# final_countdown.net
KiCad netlist of a schematic drawn in EAGLE
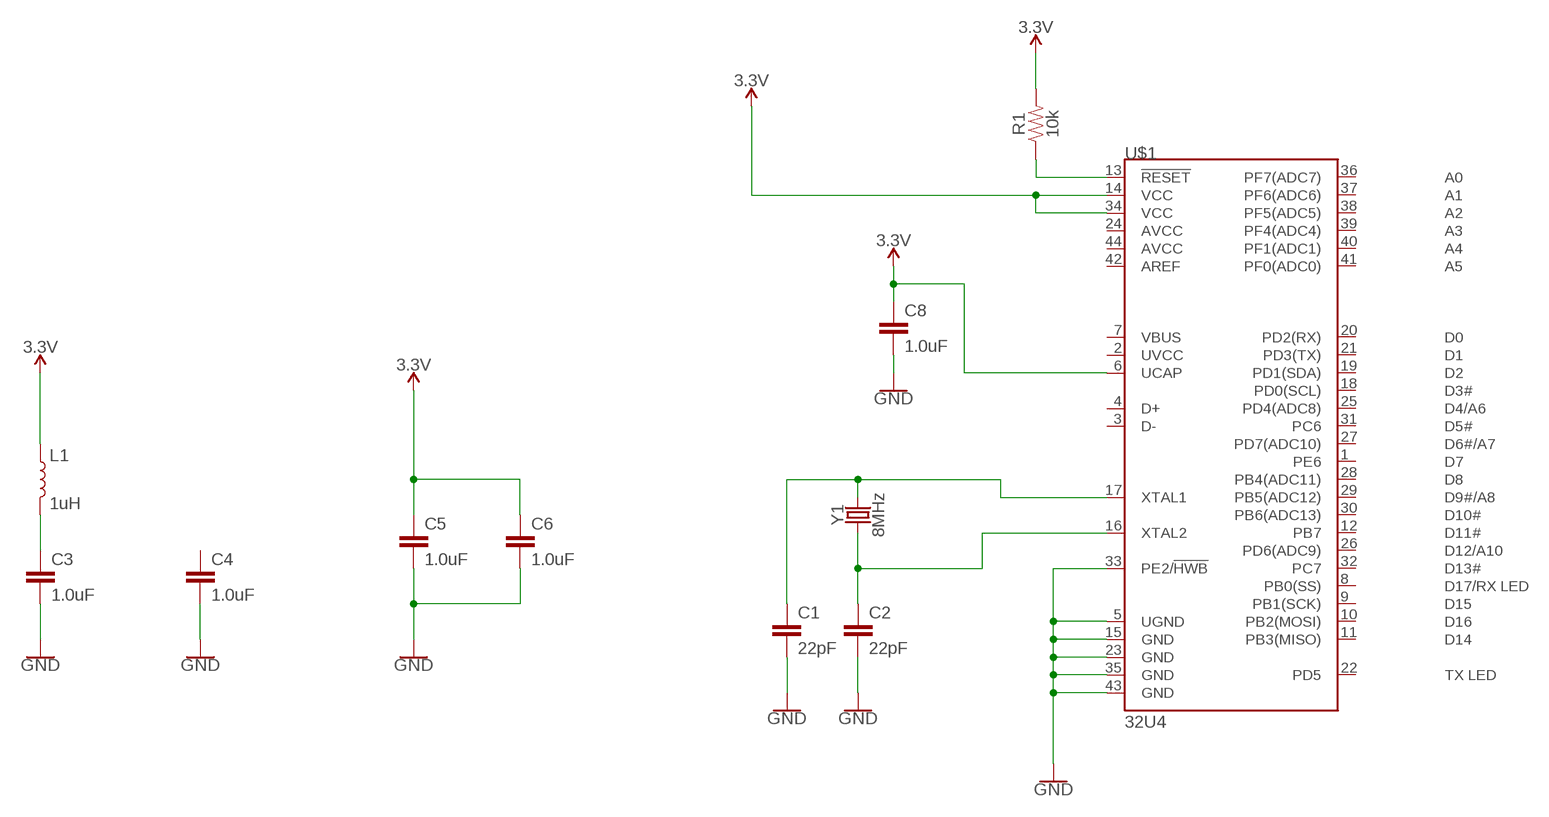
[diagram p0: schematic, sheet 1]
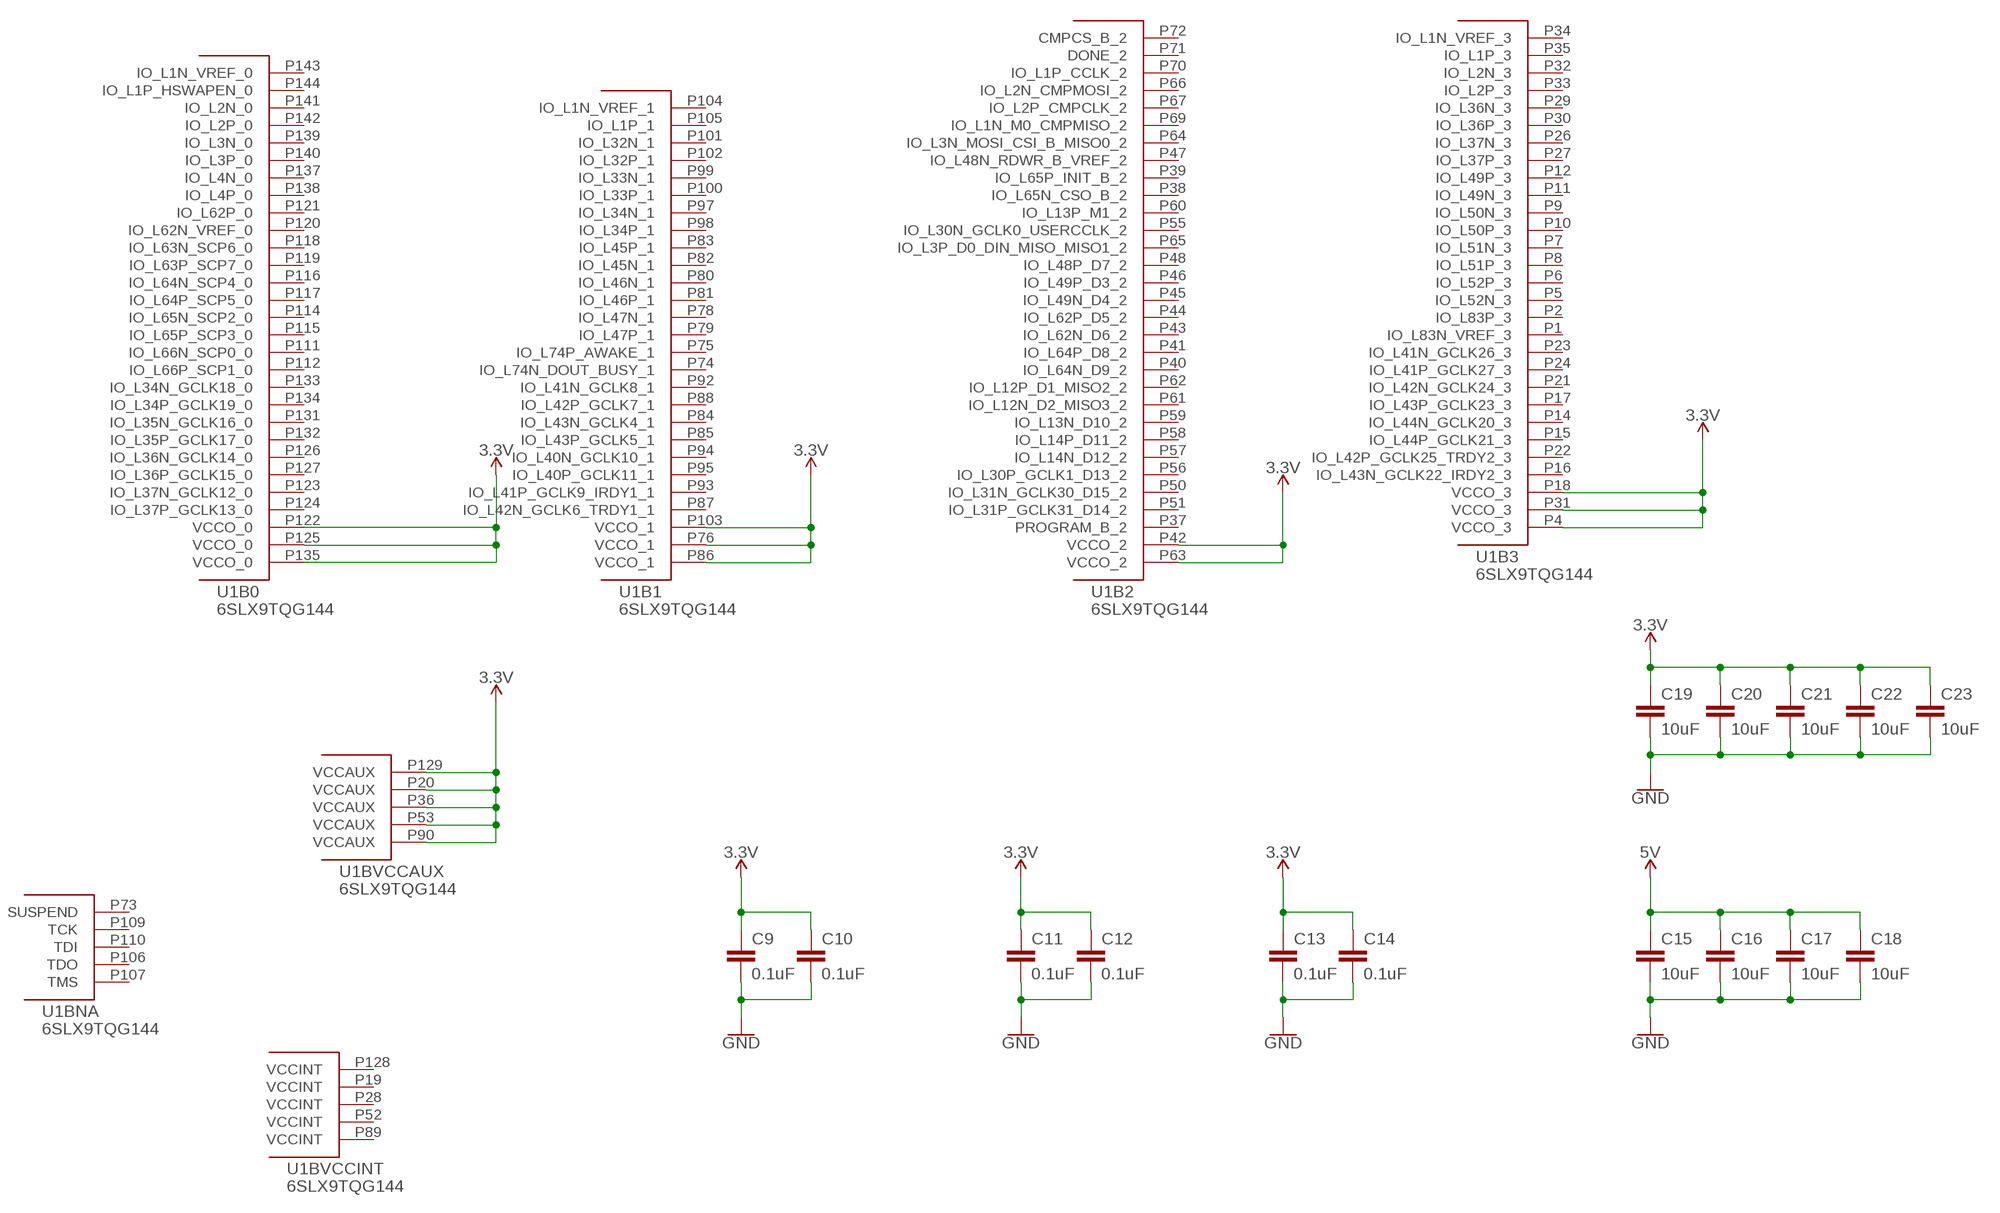
[diagram p1: schematic, sheet 2]

(export (version "E")
  (design (tool "Eeschema 10.0.6"))
  (components
    (comp (ref "C1")
      (value "22pF")
      (footprint "eagle-import:0603")
      (libsource (lib "eagle-import") (part "22PF-0603-50V-5%"))
    )
    (comp (ref "C2")
      (value "22pF")
      (footprint "eagle-import:0603")
      (libsource (lib "eagle-import") (part "22PF-0603-50V-5%"))
    )
    (comp (ref "C3")
      (value "1.0uF")
      (footprint "eagle-import:0805")
      (libsource (lib "eagle-import") (part "1.0UF-0805-25V-10%"))
    )
    (comp (ref "C4")
      (value "1.0uF")
      (footprint "eagle-import:0805")
      (libsource (lib "eagle-import") (part "1.0UF-0805-25V-10%"))
    )
    (comp (ref "C5")
      (value "1.0uF")
      (footprint "eagle-import:0805")
      (libsource (lib "eagle-import") (part "1.0UF-0805-25V-10%"))
    )
    (comp (ref "C6")
      (value "1.0uF")
      (footprint "eagle-import:0805")
      (libsource (lib "eagle-import") (part "1.0UF-0805-25V-10%"))
    )
    (comp (ref "C8")
      (value "1.0uF")
      (footprint "eagle-import:0805")
      (libsource (lib "eagle-import") (part "1.0UF-0805-25V-10%"))
    )
    (comp (ref "L1")
      (value "1uH")
      (footprint "eagle-import:INDUCTOR-SRP4020")
      (libsource (lib "eagle-import") (part "INDUCTOR-SRP4020-1UH"))
    )
    (comp (ref "R1")
      (value "10k")
      (footprint "eagle-import:0603")
      (libsource (lib "eagle-import") (part "10KOHM-0603-1/10W-1%"))
    )
    (comp (ref "U$1")
      (value "32U4")
      (footprint "eagle-import:TQFP44")
      (libsource (lib "eagle-import") (part "ATMEGA32U4TQFP-44"))
    )
    (comp (ref "Y1")
      (value "8MHz")
      (footprint "eagle-import:HC49UP")
      (libsource (lib "eagle-import") (part "CRYSTAL-8MHZSMD-HC49UP"))
    )
    (comp (ref "C9")
      (value "0.1uF")
      (footprint "eagle-import:CAP-PTH-SMALL-KIT")
      (libsource (lib "eagle-import") (part "0.1UF-KIT-EZ-50V-20%"))
    )
    (comp (ref "C10")
      (value "0.1uF")
      (footprint "eagle-import:CAP-PTH-SMALL-KIT")
      (libsource (lib "eagle-import") (part "0.1UF-KIT-EZ-50V-20%"))
    )
    (comp (ref "C11")
      (value "0.1uF")
      (footprint "eagle-import:CAP-PTH-SMALL-KIT")
      (libsource (lib "eagle-import") (part "0.1UF-KIT-EZ-50V-20%"))
    )
    (comp (ref "C12")
      (value "0.1uF")
      (footprint "eagle-import:CAP-PTH-SMALL-KIT")
      (libsource (lib "eagle-import") (part "0.1UF-KIT-EZ-50V-20%"))
    )
    (comp (ref "C13")
      (value "0.1uF")
      (footprint "eagle-import:CAP-PTH-SMALL-KIT")
      (libsource (lib "eagle-import") (part "0.1UF-KIT-EZ-50V-20%"))
    )
    (comp (ref "C14")
      (value "0.1uF")
      (footprint "eagle-import:CAP-PTH-SMALL-KIT")
      (libsource (lib "eagle-import") (part "0.1UF-KIT-EZ-50V-20%"))
    )
    (comp (ref "C15")
      (value "10uF")
      (footprint "eagle-import:0805")
      (libsource (lib "eagle-import") (part "10UF-0805-10V-10%"))
    )
    (comp (ref "C16")
      (value "10uF")
      (footprint "eagle-import:0805")
      (libsource (lib "eagle-import") (part "10UF-0805-10V-10%"))
    )
    (comp (ref "C17")
      (value "10uF")
      (footprint "eagle-import:0805")
      (libsource (lib "eagle-import") (part "10UF-0805-10V-10%"))
    )
    (comp (ref "C18")
      (value "10uF")
      (footprint "eagle-import:0805")
      (libsource (lib "eagle-import") (part "10UF-0805-10V-10%"))
    )
    (comp (ref "C19")
      (value "10uF")
      (footprint "eagle-import:0805")
      (libsource (lib "eagle-import") (part "10UF-0805-10V-10%"))
    )
    (comp (ref "C20")
      (value "10uF")
      (footprint "eagle-import:0805")
      (libsource (lib "eagle-import") (part "10UF-0805-10V-10%"))
    )
    (comp (ref "C21")
      (value "10uF")
      (footprint "eagle-import:0805")
      (libsource (lib "eagle-import") (part "10UF-0805-10V-10%"))
    )
    (comp (ref "C22")
      (value "10uF")
      (footprint "eagle-import:0805")
      (libsource (lib "eagle-import") (part "10UF-0805-10V-10%"))
    )
    (comp (ref "C23")
      (value "10uF")
      (footprint "eagle-import:0805")
      (libsource (lib "eagle-import") (part "10UF-0805-10V-10%"))
    )
    (comp (ref "U1")
      (value "6SLX9TQG144")
      (footprint "eagle-import:TQ144")
      (libsource (lib "eagle-import") (part "6SLX9TQG144"))
    )
  )
  (nets
    (net (code "1") (name "3.3V") (class "Default")
      (node (ref "C10") (pin "1") (pinfunction "1_1") (pintype "passive"))
      (node (ref "C11") (pin "1") (pinfunction "1_1") (pintype "passive"))
      (node (ref "C12") (pin "1") (pinfunction "1_1") (pintype "passive"))
      (node (ref "C13") (pin "1") (pinfunction "1_1") (pintype "passive"))
      (node (ref "C14") (pin "1") (pinfunction "1_1") (pintype "passive"))
      (node (ref "C19") (pin "1") (pinfunction "1_1") (pintype "passive"))
      (node (ref "C20") (pin "1") (pinfunction "1_1") (pintype "passive"))
      (node (ref "C21") (pin "1") (pinfunction "1_1") (pintype "passive"))
      (node (ref "C22") (pin "1") (pinfunction "1_1") (pintype "passive"))
      (node (ref "C23") (pin "1") (pinfunction "1_1") (pintype "passive"))
      (node (ref "C5") (pin "1") (pinfunction "1_1") (pintype "passive"))
      (node (ref "C6") (pin "1") (pinfunction "1_1") (pintype "passive"))
      (node (ref "C8") (pin "1") (pinfunction "1_1") (pintype "passive"))
      (node (ref "C9") (pin "1") (pinfunction "1_1") (pintype "passive"))
      (node (ref "L1") (pin "P$1") (pinfunction "1_P$1") (pintype "passive"))
      (node (ref "R1") (pin "2") (pinfunction "2_2") (pintype "passive"))
      (node (ref "U$1") (pin "14") (pinfunction "VCC_14") (pintype "bidirectional"))
      (node (ref "U$1") (pin "34") (pinfunction "VCC_34") (pintype "bidirectional"))
      (node (ref "U$1") (pin "6") (pinfunction "UCAP_6") (pintype "bidirectional"))
      (node (ref "U1") (pin "P103") (pinfunction "VCCO_1_P103") (pintype "input"))
      (node (ref "U1") (pin "P122") (pinfunction "VCCO_0_P122") (pintype "input"))
      (node (ref "U1") (pin "P125") (pinfunction "VCCO_0_P125") (pintype "input"))
      (node (ref "U1") (pin "P129") (pinfunction "VCCAUX_P129") (pintype "input"))
      (node (ref "U1") (pin "P135") (pinfunction "VCCO_0_P135") (pintype "input"))
      (node (ref "U1") (pin "P18") (pinfunction "VCCO_3_P18") (pintype "input"))
      (node (ref "U1") (pin "P20") (pinfunction "VCCAUX_P20") (pintype "input"))
      (node (ref "U1") (pin "P31") (pinfunction "VCCO_3_P31") (pintype "input"))
      (node (ref "U1") (pin "P36") (pinfunction "VCCAUX_P36") (pintype "input"))
      (node (ref "U1") (pin "P4") (pinfunction "VCCO_3_P4") (pintype "input"))
      (node (ref "U1") (pin "P42") (pinfunction "VCCO_2_P42") (pintype "input"))
      (node (ref "U1") (pin "P53") (pinfunction "VCCAUX_P53") (pintype "input"))
      (node (ref "U1") (pin "P63") (pinfunction "VCCO_2_P63") (pintype "input"))
      (node (ref "U1") (pin "P76") (pinfunction "VCCO_1_P76") (pintype "input"))
      (node (ref "U1") (pin "P86") (pinfunction "VCCO_1_P86") (pintype "input"))
      (node (ref "U1") (pin "P90") (pinfunction "VCCAUX_P90") (pintype "input"))
    )
    (net (code "2") (name "5V") (class "Default")
      (node (ref "C15") (pin "1") (pinfunction "1_1") (pintype "passive"))
      (node (ref "C16") (pin "1") (pinfunction "1_1") (pintype "passive"))
      (node (ref "C17") (pin "1") (pinfunction "1_1") (pintype "passive"))
      (node (ref "C18") (pin "1") (pinfunction "1_1") (pintype "passive"))
    )
    (net (code "3") (name "GND") (class "Default")
      (node (ref "C1") (pin "2") (pinfunction "2_2") (pintype "passive"))
      (node (ref "C10") (pin "2") (pinfunction "2_2") (pintype "passive"))
      (node (ref "C11") (pin "2") (pinfunction "2_2") (pintype "passive"))
      (node (ref "C12") (pin "2") (pinfunction "2_2") (pintype "passive"))
      (node (ref "C13") (pin "2") (pinfunction "2_2") (pintype "passive"))
      (node (ref "C14") (pin "2") (pinfunction "2_2") (pintype "passive"))
      (node (ref "C15") (pin "2") (pinfunction "2_2") (pintype "passive"))
      (node (ref "C16") (pin "2") (pinfunction "2_2") (pintype "passive"))
      (node (ref "C17") (pin "2") (pinfunction "2_2") (pintype "passive"))
      (node (ref "C18") (pin "2") (pinfunction "2_2") (pintype "passive"))
      (node (ref "C19") (pin "2") (pinfunction "2_2") (pintype "passive"))
      (node (ref "C2") (pin "2") (pinfunction "2_2") (pintype "passive"))
      (node (ref "C20") (pin "2") (pinfunction "2_2") (pintype "passive"))
      (node (ref "C21") (pin "2") (pinfunction "2_2") (pintype "passive"))
      (node (ref "C22") (pin "2") (pinfunction "2_2") (pintype "passive"))
      (node (ref "C23") (pin "2") (pinfunction "2_2") (pintype "passive"))
      (node (ref "C3") (pin "2") (pinfunction "2_2") (pintype "passive"))
      (node (ref "C4") (pin "2") (pinfunction "2_2") (pintype "passive"))
      (node (ref "C5") (pin "2") (pinfunction "2_2") (pintype "passive"))
      (node (ref "C6") (pin "2") (pinfunction "2_2") (pintype "passive"))
      (node (ref "C8") (pin "2") (pinfunction "2_2") (pintype "passive"))
      (node (ref "C9") (pin "2") (pinfunction "2_2") (pintype "passive"))
      (node (ref "U$1") (pin "15") (pinfunction "GND_15") (pintype "bidirectional"))
      (node (ref "U$1") (pin "23") (pinfunction "GND_23") (pintype "bidirectional"))
      (node (ref "U$1") (pin "33") (pinfunction "PE2/~{HWB}_33") (pintype "bidirectional"))
      (node (ref "U$1") (pin "35") (pinfunction "GND_35") (pintype "bidirectional"))
      (node (ref "U$1") (pin "43") (pinfunction "GND_43") (pintype "bidirectional"))
      (node (ref "U$1") (pin "5") (pinfunction "UGND_5") (pintype "bidirectional"))
    )
    (net (code "4") (name "Net-(L1-2)") (class "Default")
      (node (ref "C3") (pin "1") (pinfunction "1_1") (pintype "passive"))
      (node (ref "L1") (pin "P$2") (pinfunction "2_P$2") (pintype "passive"))
    )
    (net (code "5") (name "Net-(U$1-XTAL1)") (class "Default")
      (node (ref "C1") (pin "1") (pinfunction "1_1") (pintype "passive"))
      (node (ref "U$1") (pin "17") (pinfunction "XTAL1_17") (pintype "bidirectional"))
      (node (ref "Y1") (pin "2") (pinfunction "2_2") (pintype "passive"))
    )
    (net (code "6") (name "Net-(U$1-XTAL2)") (class "Default")
      (node (ref "C2") (pin "1") (pinfunction "1_1") (pintype "passive"))
      (node (ref "U$1") (pin "16") (pinfunction "XTAL2_16") (pintype "bidirectional"))
      (node (ref "Y1") (pin "1") (pinfunction "1_1") (pintype "passive"))
    )
    (net (code "7") (name "Net-(U$1-~{RESET})") (class "Default")
      (node (ref "R1") (pin "1") (pinfunction "1_1") (pintype "passive"))
      (node (ref "U$1") (pin "13") (pinfunction "~{RESET}_13") (pintype "bidirectional"))
    )
    (net (code "8") (name "unconnected-(C4-Pad1)") (class "Default")
      (node (ref "C4") (pin "1") (pinfunction "1_1") (pintype "passive"))
    )
    (net (code "9") (name "unconnected-(U$1-AREF-Pad42)") (class "Default")
      (node (ref "U$1") (pin "42") (pinfunction "AREF_42") (pintype "bidirectional"))
    )
    (net (code "10") (name "unconnected-(U$1-AVCC-Pad24)") (class "Default")
      (node (ref "U$1") (pin "24") (pinfunction "AVCC_24") (pintype "bidirectional"))
    )
    (net (code "11") (name "unconnected-(U$1-AVCC-Pad44)") (class "Default")
      (node (ref "U$1") (pin "44") (pinfunction "AVCC_44") (pintype "bidirectional"))
    )
    (net (code "12") (name "unconnected-(U$1-D+-Pad4)") (class "Default")
      (node (ref "U$1") (pin "4") (pinfunction "D+_4") (pintype "bidirectional"))
    )
    (net (code "13") (name "unconnected-(U$1-D--Pad3)") (class "Default")
      (node (ref "U$1") (pin "3") (pinfunction "D-_3") (pintype "bidirectional"))
    )
    (net (code "14") (name "unconnected-(U$1-PB0(SS)-Pad8)") (class "Default")
      (node (ref "U$1") (pin "8") (pinfunction "PB0(SS)_8") (pintype "bidirectional"))
    )
    (net (code "15") (name "unconnected-(U$1-PB1(SCK)-Pad9)") (class "Default")
      (node (ref "U$1") (pin "9") (pinfunction "PB1(SCK)_9") (pintype "bidirectional"))
    )
    (net (code "16") (name "unconnected-(U$1-PB2(MOSI)-Pad10)") (class "Default")
      (node (ref "U$1") (pin "10") (pinfunction "PB2(MOSI)_10") (pintype "bidirectional"))
    )
    (net (code "17") (name "unconnected-(U$1-PB3(MISO)-Pad11)") (class "Default")
      (node (ref "U$1") (pin "11") (pinfunction "PB3(MISO)_11") (pintype "bidirectional"))
    )
    (net (code "18") (name "unconnected-(U$1-PB4(ADC11)-Pad28)") (class "Default")
      (node (ref "U$1") (pin "28") (pinfunction "PB4(ADC11)_28") (pintype "bidirectional"))
    )
    (net (code "19") (name "unconnected-(U$1-PB5(ADC12)-Pad29)") (class "Default")
      (node (ref "U$1") (pin "29") (pinfunction "PB5(ADC12)_29") (pintype "bidirectional"))
    )
    (net (code "20") (name "unconnected-(U$1-PB6(ADC13)-Pad30)") (class "Default")
      (node (ref "U$1") (pin "30") (pinfunction "PB6(ADC13)_30") (pintype "bidirectional"))
    )
    (net (code "21") (name "unconnected-(U$1-PB7-Pad12)") (class "Default")
      (node (ref "U$1") (pin "12") (pinfunction "PB7_12") (pintype "bidirectional"))
    )
    (net (code "22") (name "unconnected-(U$1-PC6-Pad31)") (class "Default")
      (node (ref "U$1") (pin "31") (pinfunction "PC6_31") (pintype "bidirectional"))
    )
    (net (code "23") (name "unconnected-(U$1-PC7-Pad32)") (class "Default")
      (node (ref "U$1") (pin "32") (pinfunction "PC7_32") (pintype "bidirectional"))
    )
    (net (code "24") (name "unconnected-(U$1-PD0(SCL)-Pad18)") (class "Default")
      (node (ref "U$1") (pin "18") (pinfunction "PD0(SCL)_18") (pintype "bidirectional"))
    )
    (net (code "25") (name "unconnected-(U$1-PD1(SDA)-Pad19)") (class "Default")
      (node (ref "U$1") (pin "19") (pinfunction "PD1(SDA)_19") (pintype "bidirectional"))
    )
    (net (code "26") (name "unconnected-(U$1-PD2(RX)-Pad20)") (class "Default")
      (node (ref "U$1") (pin "20") (pinfunction "PD2(RX)_20") (pintype "bidirectional"))
    )
    (net (code "27") (name "unconnected-(U$1-PD3(TX)-Pad21)") (class "Default")
      (node (ref "U$1") (pin "21") (pinfunction "PD3(TX)_21") (pintype "bidirectional"))
    )
    (net (code "28") (name "unconnected-(U$1-PD4(ADC8)-Pad25)") (class "Default")
      (node (ref "U$1") (pin "25") (pinfunction "PD4(ADC8)_25") (pintype "bidirectional"))
    )
    (net (code "29") (name "unconnected-(U$1-PD5-Pad22)") (class "Default")
      (node (ref "U$1") (pin "22") (pinfunction "PD5_22") (pintype "bidirectional"))
    )
    (net (code "30") (name "unconnected-(U$1-PD6(ADC9)-Pad26)") (class "Default")
      (node (ref "U$1") (pin "26") (pinfunction "PD6(ADC9)_26") (pintype "bidirectional"))
    )
    (net (code "31") (name "unconnected-(U$1-PD7(ADC10)-Pad27)") (class "Default")
      (node (ref "U$1") (pin "27") (pinfunction "PD7(ADC10)_27") (pintype "bidirectional"))
    )
    (net (code "32") (name "unconnected-(U$1-PE6-Pad1)") (class "Default")
      (node (ref "U$1") (pin "1") (pinfunction "PE6_1") (pintype "bidirectional"))
    )
    (net (code "33") (name "unconnected-(U$1-PF0(ADC0)-Pad41)") (class "Default")
      (node (ref "U$1") (pin "41") (pinfunction "PF0(ADC0)_41") (pintype "bidirectional"))
    )
    (net (code "34") (name "unconnected-(U$1-PF1(ADC1)-Pad40)") (class "Default")
      (node (ref "U$1") (pin "40") (pinfunction "PF1(ADC1)_40") (pintype "bidirectional"))
    )
    (net (code "35") (name "unconnected-(U$1-PF4(ADC4)-Pad39)") (class "Default")
      (node (ref "U$1") (pin "39") (pinfunction "PF4(ADC4)_39") (pintype "bidirectional"))
    )
    (net (code "36") (name "unconnected-(U$1-PF5(ADC5)-Pad38)") (class "Default")
      (node (ref "U$1") (pin "38") (pinfunction "PF5(ADC5)_38") (pintype "bidirectional"))
    )
    (net (code "37") (name "unconnected-(U$1-PF6(ADC6)-Pad37)") (class "Default")
      (node (ref "U$1") (pin "37") (pinfunction "PF6(ADC6)_37") (pintype "bidirectional"))
    )
    (net (code "38") (name "unconnected-(U$1-PF7(ADC7)-Pad36)") (class "Default")
      (node (ref "U$1") (pin "36") (pinfunction "PF7(ADC7)_36") (pintype "bidirectional"))
    )
    (net (code "39") (name "unconnected-(U$1-UVCC-Pad2)") (class "Default")
      (node (ref "U$1") (pin "2") (pinfunction "UVCC_2") (pintype "bidirectional"))
    )
    (net (code "40") (name "unconnected-(U$1-VBUS-Pad7)") (class "Default")
      (node (ref "U$1") (pin "7") (pinfunction "VBUS_7") (pintype "bidirectional"))
    )
    (net (code "41") (name "unconnected-(U1A-IO_L1N_VREF_0-PadP143)") (class "Default")
      (node (ref "U1") (pin "P143") (pinfunction "IO_L1N_VREF_0_P143") (pintype "bidirectional"))
    )
    (net (code "42") (name "unconnected-(U1A-IO_L1P_HSWAPEN_0-PadP144)") (class "Default")
      (node (ref "U1") (pin "P144") (pinfunction "IO_L1P_HSWAPEN_0_P144") (pintype "bidirectional"))
    )
    (net (code "43") (name "unconnected-(U1A-IO_L2N_0-PadP141)") (class "Default")
      (node (ref "U1") (pin "P141") (pinfunction "IO_L2N_0_P141") (pintype "bidirectional"))
    )
    (net (code "44") (name "unconnected-(U1A-IO_L2P_0-PadP142)") (class "Default")
      (node (ref "U1") (pin "P142") (pinfunction "IO_L2P_0_P142") (pintype "bidirectional"))
    )
    (net (code "45") (name "unconnected-(U1A-IO_L3N_0-PadP139)") (class "Default")
      (node (ref "U1") (pin "P139") (pinfunction "IO_L3N_0_P139") (pintype "bidirectional"))
    )
    (net (code "46") (name "unconnected-(U1A-IO_L3P_0-PadP140)") (class "Default")
      (node (ref "U1") (pin "P140") (pinfunction "IO_L3P_0_P140") (pintype "bidirectional"))
    )
    (net (code "47") (name "unconnected-(U1A-IO_L4N_0-PadP137)") (class "Default")
      (node (ref "U1") (pin "P137") (pinfunction "IO_L4N_0_P137") (pintype "bidirectional"))
    )
    (net (code "48") (name "unconnected-(U1A-IO_L4P_0-PadP138)") (class "Default")
      (node (ref "U1") (pin "P138") (pinfunction "IO_L4P_0_P138") (pintype "bidirectional"))
    )
    (net (code "49") (name "unconnected-(U1A-IO_L34N_GCLK18_0-PadP133)") (class "Default")
      (node (ref "U1") (pin "P133") (pinfunction "IO_L34N_GCLK18_0_P133") (pintype "bidirectional"))
    )
    (net (code "50") (name "unconnected-(U1A-IO_L34P_GCLK19_0-PadP134)") (class "Default")
      (node (ref "U1") (pin "P134") (pinfunction "IO_L34P_GCLK19_0_P134") (pintype "bidirectional"))
    )
    (net (code "51") (name "unconnected-(U1A-IO_L35N_GCLK16_0-PadP131)") (class "Default")
      (node (ref "U1") (pin "P131") (pinfunction "IO_L35N_GCLK16_0_P131") (pintype "bidirectional"))
    )
    (net (code "52") (name "unconnected-(U1A-IO_L35P_GCLK17_0-PadP132)") (class "Default")
      (node (ref "U1") (pin "P132") (pinfunction "IO_L35P_GCLK17_0_P132") (pintype "bidirectional"))
    )
    (net (code "53") (name "unconnected-(U1A-IO_L36N_GCLK14_0-PadP126)") (class "Default")
      (node (ref "U1") (pin "P126") (pinfunction "IO_L36N_GCLK14_0_P126") (pintype "bidirectional"))
    )
    (net (code "54") (name "unconnected-(U1A-IO_L36P_GCLK15_0-PadP127)") (class "Default")
      (node (ref "U1") (pin "P127") (pinfunction "IO_L36P_GCLK15_0_P127") (pintype "bidirectional"))
    )
    (net (code "55") (name "unconnected-(U1A-IO_L37N_GCLK12_0-PadP123)") (class "Default")
      (node (ref "U1") (pin "P123") (pinfunction "IO_L37N_GCLK12_0_P123") (pintype "bidirectional"))
    )
    (net (code "56") (name "unconnected-(U1A-IO_L37P_GCLK13_0-PadP124)") (class "Default")
      (node (ref "U1") (pin "P124") (pinfunction "IO_L37P_GCLK13_0_P124") (pintype "bidirectional"))
    )
    (net (code "57") (name "unconnected-(U1A-IO_L62N_VREF_0-PadP120)") (class "Default")
      (node (ref "U1") (pin "P120") (pinfunction "IO_L62N_VREF_0_P120") (pintype "bidirectional"))
    )
    (net (code "58") (name "unconnected-(U1A-IO_L62P_0-PadP121)") (class "Default")
      (node (ref "U1") (pin "P121") (pinfunction "IO_L62P_0_P121") (pintype "bidirectional"))
    )
    (net (code "59") (name "unconnected-(U1A-IO_L63N_SCP6_0-PadP118)") (class "Default")
      (node (ref "U1") (pin "P118") (pinfunction "IO_L63N_SCP6_0_P118") (pintype "bidirectional"))
    )
    (net (code "60") (name "unconnected-(U1A-IO_L63P_SCP7_0-PadP119)") (class "Default")
      (node (ref "U1") (pin "P119") (pinfunction "IO_L63P_SCP7_0_P119") (pintype "bidirectional"))
    )
    (net (code "61") (name "unconnected-(U1A-IO_L64N_SCP4_0-PadP116)") (class "Default")
      (node (ref "U1") (pin "P116") (pinfunction "IO_L64N_SCP4_0_P116") (pintype "bidirectional"))
    )
    (net (code "62") (name "unconnected-(U1A-IO_L64P_SCP5_0-PadP117)") (class "Default")
      (node (ref "U1") (pin "P117") (pinfunction "IO_L64P_SCP5_0_P117") (pintype "bidirectional"))
    )
    (net (code "63") (name "unconnected-(U1A-IO_L65N_SCP2_0-PadP114)") (class "Default")
      (node (ref "U1") (pin "P114") (pinfunction "IO_L65N_SCP2_0_P114") (pintype "bidirectional"))
    )
    (net (code "64") (name "unconnected-(U1A-IO_L65P_SCP3_0-PadP115)") (class "Default")
      (node (ref "U1") (pin "P115") (pinfunction "IO_L65P_SCP3_0_P115") (pintype "bidirectional"))
    )
    (net (code "65") (name "unconnected-(U1A-IO_L66N_SCP0_0-PadP111)") (class "Default")
      (node (ref "U1") (pin "P111") (pinfunction "IO_L66N_SCP0_0_P111") (pintype "bidirectional"))
    )
    (net (code "66") (name "unconnected-(U1A-IO_L66P_SCP1_0-PadP112)") (class "Default")
      (node (ref "U1") (pin "P112") (pinfunction "IO_L66P_SCP1_0_P112") (pintype "bidirectional"))
    )
    (net (code "67") (name "unconnected-(U1B-IO_L1N_VREF_1-PadP104)") (class "Default")
      (node (ref "U1") (pin "P104") (pinfunction "IO_L1N_VREF_1_P104") (pintype "bidirectional"))
    )
    (net (code "68") (name "unconnected-(U1B-IO_L1P_1-PadP105)") (class "Default")
      (node (ref "U1") (pin "P105") (pinfunction "IO_L1P_1_P105") (pintype "bidirectional"))
    )
    (net (code "69") (name "unconnected-(U1B-IO_L32N_1-PadP101)") (class "Default")
      (node (ref "U1") (pin "P101") (pinfunction "IO_L32N_1_P101") (pintype "bidirectional"))
    )
    (net (code "70") (name "unconnected-(U1B-IO_L32P_1-PadP102)") (class "Default")
      (node (ref "U1") (pin "P102") (pinfunction "IO_L32P_1_P102") (pintype "bidirectional"))
    )
    (net (code "71") (name "unconnected-(U1B-IO_L33N_1-PadP99)") (class "Default")
      (node (ref "U1") (pin "P99") (pinfunction "IO_L33N_1_P99") (pintype "bidirectional"))
    )
    (net (code "72") (name "unconnected-(U1B-IO_L33P_1-PadP100)") (class "Default")
      (node (ref "U1") (pin "P100") (pinfunction "IO_L33P_1_P100") (pintype "bidirectional"))
    )
    (net (code "73") (name "unconnected-(U1B-IO_L34N_1-PadP97)") (class "Default")
      (node (ref "U1") (pin "P97") (pinfunction "IO_L34N_1_P97") (pintype "bidirectional"))
    )
    (net (code "74") (name "unconnected-(U1B-IO_L34P_1-PadP98)") (class "Default")
      (node (ref "U1") (pin "P98") (pinfunction "IO_L34P_1_P98") (pintype "bidirectional"))
    )
    (net (code "75") (name "unconnected-(U1B-IO_L40N_GCLK10_1-PadP94)") (class "Default")
      (node (ref "U1") (pin "P94") (pinfunction "IO_L40N_GCLK10_1_P94") (pintype "bidirectional"))
    )
    (net (code "76") (name "unconnected-(U1B-IO_L40P_GCLK11_1-PadP95)") (class "Default")
      (node (ref "U1") (pin "P95") (pinfunction "IO_L40P_GCLK11_1_P95") (pintype "bidirectional"))
    )
    (net (code "77") (name "unconnected-(U1B-IO_L41N_GCLK8_1-PadP92)") (class "Default")
      (node (ref "U1") (pin "P92") (pinfunction "IO_L41N_GCLK8_1_P92") (pintype "bidirectional"))
    )
    (net (code "78") (name "unconnected-(U1B-IO_L41P_GCLK9_IRDY1_1-PadP93)") (class "Default")
      (node (ref "U1") (pin "P93") (pinfunction "IO_L41P_GCLK9_IRDY1_1_P93") (pintype "bidirectional"))
    )
    (net (code "79") (name "unconnected-(U1B-IO_L42N_GCLK6_TRDY1_1-PadP87)") (class "Default")
      (node (ref "U1") (pin "P87") (pinfunction "IO_L42N_GCLK6_TRDY1_1_P87") (pintype "bidirectional"))
    )
    (net (code "80") (name "unconnected-(U1B-IO_L42P_GCLK7_1-PadP88)") (class "Default")
      (node (ref "U1") (pin "P88") (pinfunction "IO_L42P_GCLK7_1_P88") (pintype "bidirectional"))
    )
    (net (code "81") (name "unconnected-(U1B-IO_L43N_GCLK4_1-PadP84)") (class "Default")
      (node (ref "U1") (pin "P84") (pinfunction "IO_L43N_GCLK4_1_P84") (pintype "bidirectional"))
    )
    (net (code "82") (name "unconnected-(U1B-IO_L43P_GCLK5_1-PadP85)") (class "Default")
      (node (ref "U1") (pin "P85") (pinfunction "IO_L43P_GCLK5_1_P85") (pintype "bidirectional"))
    )
    (net (code "83") (name "unconnected-(U1B-IO_L45N_1-PadP82)") (class "Default")
      (node (ref "U1") (pin "P82") (pinfunction "IO_L45N_1_P82") (pintype "bidirectional"))
    )
    (net (code "84") (name "unconnected-(U1B-IO_L45P_1-PadP83)") (class "Default")
      (node (ref "U1") (pin "P83") (pinfunction "IO_L45P_1_P83") (pintype "bidirectional"))
    )
    (net (code "85") (name "unconnected-(U1B-IO_L46N_1-PadP80)") (class "Default")
      (node (ref "U1") (pin "P80") (pinfunction "IO_L46N_1_P80") (pintype "bidirectional"))
    )
    (net (code "86") (name "unconnected-(U1B-IO_L46P_1-PadP81)") (class "Default")
      (node (ref "U1") (pin "P81") (pinfunction "IO_L46P_1_P81") (pintype "bidirectional"))
    )
    (net (code "87") (name "unconnected-(U1B-IO_L47N_1-PadP78)") (class "Default")
      (node (ref "U1") (pin "P78") (pinfunction "IO_L47N_1_P78") (pintype "bidirectional"))
    )
    (net (code "88") (name "unconnected-(U1B-IO_L47P_1-PadP79)") (class "Default")
      (node (ref "U1") (pin "P79") (pinfunction "IO_L47P_1_P79") (pintype "bidirectional"))
    )
    (net (code "89") (name "unconnected-(U1B-IO_L74N_DOUT_BUSY_1-PadP74)") (class "Default")
      (node (ref "U1") (pin "P74") (pinfunction "IO_L74N_DOUT_BUSY_1_P74") (pintype "bidirectional"))
    )
    (net (code "90") (name "unconnected-(U1B-IO_L74P_AWAKE_1-PadP75)") (class "Default")
      (node (ref "U1") (pin "P75") (pinfunction "IO_L74P_AWAKE_1_P75") (pintype "bidirectional"))
    )
    (net (code "91") (name "unconnected-(U1C-CMPCS_B_2-PadP72)") (class "Default")
      (node (ref "U1") (pin "P72") (pinfunction "CMPCS_B_2_P72") (pintype "bidirectional"))
    )
    (net (code "92") (name "unconnected-(U1C-DONE_2-PadP71)") (class "Default")
      (node (ref "U1") (pin "P71") (pinfunction "DONE_2_P71") (pintype "bidirectional"))
    )
    (net (code "93") (name "unconnected-(U1C-IO_L1N_M0_CMPMISO_2-PadP69)") (class "Default")
      (node (ref "U1") (pin "P69") (pinfunction "IO_L1N_M0_CMPMISO_2_P69") (pintype "bidirectional"))
    )
    (net (code "94") (name "unconnected-(U1C-IO_L1P_CCLK_2-PadP70)") (class "Default")
      (node (ref "U1") (pin "P70") (pinfunction "IO_L1P_CCLK_2_P70") (pintype "bidirectional"))
    )
    (net (code "95") (name "unconnected-(U1C-IO_L2N_CMPMOSI_2-PadP66)") (class "Default")
      (node (ref "U1") (pin "P66") (pinfunction "IO_L2N_CMPMOSI_2_P66") (pintype "bidirectional"))
    )
    (net (code "96") (name "unconnected-(U1C-IO_L2P_CMPCLK_2-PadP67)") (class "Default")
      (node (ref "U1") (pin "P67") (pinfunction "IO_L2P_CMPCLK_2_P67") (pintype "bidirectional"))
    )
    (net (code "97") (name "unconnected-(U1C-IO_L3N_MOSI_CSI_B_MISO0_2-PadP64)") (class "Default")
      (node (ref "U1") (pin "P64") (pinfunction "IO_L3N_MOSI_CSI_B_MISO0_2_P64") (pintype "bidirectional"))
    )
    (net (code "98") (name "unconnected-(U1C-IO_L3P_D0_DIN_MISO_MISO1_2-PadP65)") (class "Default")
      (node (ref "U1") (pin "P65") (pinfunction "IO_L3P_D0_DIN_MISO_MISO1_2_P65") (pintype "bidirectional"))
    )
    (net (code "99") (name "unconnected-(U1C-IO_L12N_D2_MISO3_2-PadP61)") (class "Default")
      (node (ref "U1") (pin "P61") (pinfunction "IO_L12N_D2_MISO3_2_P61") (pintype "bidirectional"))
    )
    (net (code "100") (name "unconnected-(U1C-IO_L12P_D1_MISO2_2-PadP62)") (class "Default")
      (node (ref "U1") (pin "P62") (pinfunction "IO_L12P_D1_MISO2_2_P62") (pintype "bidirectional"))
    )
    (net (code "101") (name "unconnected-(U1C-IO_L13N_D10_2-PadP59)") (class "Default")
      (node (ref "U1") (pin "P59") (pinfunction "IO_L13N_D10_2_P59") (pintype "bidirectional"))
    )
    (net (code "102") (name "unconnected-(U1C-IO_L13P_M1_2-PadP60)") (class "Default")
      (node (ref "U1") (pin "P60") (pinfunction "IO_L13P_M1_2_P60") (pintype "bidirectional"))
    )
    (net (code "103") (name "unconnected-(U1C-IO_L14N_D12_2-PadP57)") (class "Default")
      (node (ref "U1") (pin "P57") (pinfunction "IO_L14N_D12_2_P57") (pintype "bidirectional"))
    )
    (net (code "104") (name "unconnected-(U1C-IO_L14P_D11_2-PadP58)") (class "Default")
      (node (ref "U1") (pin "P58") (pinfunction "IO_L14P_D11_2_P58") (pintype "bidirectional"))
    )
    (net (code "105") (name "unconnected-(U1C-IO_L30N_GCLK0_USERCCLK_2-PadP55)") (class "Default")
      (node (ref "U1") (pin "P55") (pinfunction "IO_L30N_GCLK0_USERCCLK_2_P55") (pintype "bidirectional"))
    )
    (net (code "106") (name "unconnected-(U1C-IO_L30P_GCLK1_D13_2-PadP56)") (class "Default")
      (node (ref "U1") (pin "P56") (pinfunction "IO_L30P_GCLK1_D13_2_P56") (pintype "bidirectional"))
    )
    (net (code "107") (name "unconnected-(U1C-IO_L31N_GCLK30_D15_2-PadP50)") (class "Default")
      (node (ref "U1") (pin "P50") (pinfunction "IO_L31N_GCLK30_D15_2_P50") (pintype "bidirectional"))
    )
    (net (code "108") (name "unconnected-(U1C-IO_L31P_GCLK31_D14_2-PadP51)") (class "Default")
      (node (ref "U1") (pin "P51") (pinfunction "IO_L31P_GCLK31_D14_2_P51") (pintype "bidirectional"))
    )
    (net (code "109") (name "unconnected-(U1C-IO_L48N_RDWR_B_VREF_2-PadP47)") (class "Default")
      (node (ref "U1") (pin "P47") (pinfunction "IO_L48N_RDWR_B_VREF_2_P47") (pintype "bidirectional"))
    )
    (net (code "110") (name "unconnected-(U1C-IO_L48P_D7_2-PadP48)") (class "Default")
      (node (ref "U1") (pin "P48") (pinfunction "IO_L48P_D7_2_P48") (pintype "bidirectional"))
    )
    (net (code "111") (name "unconnected-(U1C-IO_L49N_D4_2-PadP45)") (class "Default")
      (node (ref "U1") (pin "P45") (pinfunction "IO_L49N_D4_2_P45") (pintype "bidirectional"))
    )
    (net (code "112") (name "unconnected-(U1C-IO_L49P_D3_2-PadP46)") (class "Default")
      (node (ref "U1") (pin "P46") (pinfunction "IO_L49P_D3_2_P46") (pintype "bidirectional"))
    )
    (net (code "113") (name "unconnected-(U1C-IO_L62N_D6_2-PadP43)") (class "Default")
      (node (ref "U1") (pin "P43") (pinfunction "IO_L62N_D6_2_P43") (pintype "bidirectional"))
    )
    (net (code "114") (name "unconnected-(U1C-IO_L62P_D5_2-PadP44)") (class "Default")
      (node (ref "U1") (pin "P44") (pinfunction "IO_L62P_D5_2_P44") (pintype "bidirectional"))
    )
    (net (code "115") (name "unconnected-(U1C-IO_L64N_D9_2-PadP40)") (class "Default")
      (node (ref "U1") (pin "P40") (pinfunction "IO_L64N_D9_2_P40") (pintype "bidirectional"))
    )
    (net (code "116") (name "unconnected-(U1C-IO_L64P_D8_2-PadP41)") (class "Default")
      (node (ref "U1") (pin "P41") (pinfunction "IO_L64P_D8_2_P41") (pintype "bidirectional"))
    )
    (net (code "117") (name "unconnected-(U1C-IO_L65N_CSO_B_2-PadP38)") (class "Default")
      (node (ref "U1") (pin "P38") (pinfunction "IO_L65N_CSO_B_2_P38") (pintype "bidirectional"))
    )
    (net (code "118") (name "unconnected-(U1C-IO_L65P_INIT_B_2-PadP39)") (class "Default")
      (node (ref "U1") (pin "P39") (pinfunction "IO_L65P_INIT_B_2_P39") (pintype "bidirectional"))
    )
    (net (code "119") (name "unconnected-(U1C-PROGRAM_B_2-PadP37)") (class "Default")
      (node (ref "U1") (pin "P37") (pinfunction "PROGRAM_B_2_P37") (pintype "bidirectional"))
    )
    (net (code "120") (name "unconnected-(U1D-IO_L1N_VREF_3-PadP34)") (class "Default")
      (node (ref "U1") (pin "P34") (pinfunction "IO_L1N_VREF_3_P34") (pintype "bidirectional"))
    )
    (net (code "121") (name "unconnected-(U1D-IO_L1P_3-PadP35)") (class "Default")
      (node (ref "U1") (pin "P35") (pinfunction "IO_L1P_3_P35") (pintype "bidirectional"))
    )
    (net (code "122") (name "unconnected-(U1D-IO_L2N_3-PadP32)") (class "Default")
      (node (ref "U1") (pin "P32") (pinfunction "IO_L2N_3_P32") (pintype "bidirectional"))
    )
    (net (code "123") (name "unconnected-(U1D-IO_L2P_3-PadP33)") (class "Default")
      (node (ref "U1") (pin "P33") (pinfunction "IO_L2P_3_P33") (pintype "bidirectional"))
    )
    (net (code "124") (name "unconnected-(U1D-IO_L36N_3-PadP29)") (class "Default")
      (node (ref "U1") (pin "P29") (pinfunction "IO_L36N_3_P29") (pintype "bidirectional"))
    )
    (net (code "125") (name "unconnected-(U1D-IO_L36P_3-PadP30)") (class "Default")
      (node (ref "U1") (pin "P30") (pinfunction "IO_L36P_3_P30") (pintype "bidirectional"))
    )
    (net (code "126") (name "unconnected-(U1D-IO_L37N_3-PadP26)") (class "Default")
      (node (ref "U1") (pin "P26") (pinfunction "IO_L37N_3_P26") (pintype "bidirectional"))
    )
    (net (code "127") (name "unconnected-(U1D-IO_L37P_3-PadP27)") (class "Default")
      (node (ref "U1") (pin "P27") (pinfunction "IO_L37P_3_P27") (pintype "bidirectional"))
    )
    (net (code "128") (name "unconnected-(U1D-IO_L41N_GCLK26_3-PadP23)") (class "Default")
      (node (ref "U1") (pin "P23") (pinfunction "IO_L41N_GCLK26_3_P23") (pintype "bidirectional"))
    )
    (net (code "129") (name "unconnected-(U1D-IO_L41P_GCLK27_3-PadP24)") (class "Default")
      (node (ref "U1") (pin "P24") (pinfunction "IO_L41P_GCLK27_3_P24") (pintype "bidirectional"))
    )
    (net (code "130") (name "unconnected-(U1D-IO_L42N_GCLK24_3-PadP21)") (class "Default")
      (node (ref "U1") (pin "P21") (pinfunction "IO_L42N_GCLK24_3_P21") (pintype "bidirectional"))
    )
    (net (code "131") (name "unconnected-(U1D-IO_L42P_GCLK25_TRDY2_3-PadP22)") (class "Default")
      (node (ref "U1") (pin "P22") (pinfunction "IO_L42P_GCLK25_TRDY2_3_P22") (pintype "bidirectional"))
    )
    (net (code "132") (name "unconnected-(U1D-IO_L43N_GCLK22_IRDY2_3-PadP16)") (class "Default")
      (node (ref "U1") (pin "P16") (pinfunction "IO_L43N_GCLK22_IRDY2_3_P16") (pintype "bidirectional"))
    )
    (net (code "133") (name "unconnected-(U1D-IO_L43P_GCLK23_3-PadP17)") (class "Default")
      (node (ref "U1") (pin "P17") (pinfunction "IO_L43P_GCLK23_3_P17") (pintype "bidirectional"))
    )
    (net (code "134") (name "unconnected-(U1D-IO_L44N_GCLK20_3-PadP14)") (class "Default")
      (node (ref "U1") (pin "P14") (pinfunction "IO_L44N_GCLK20_3_P14") (pintype "bidirectional"))
    )
    (net (code "135") (name "unconnected-(U1D-IO_L44P_GCLK21_3-PadP15)") (class "Default")
      (node (ref "U1") (pin "P15") (pinfunction "IO_L44P_GCLK21_3_P15") (pintype "bidirectional"))
    )
    (net (code "136") (name "unconnected-(U1D-IO_L49N_3-PadP11)") (class "Default")
      (node (ref "U1") (pin "P11") (pinfunction "IO_L49N_3_P11") (pintype "bidirectional"))
    )
    (net (code "137") (name "unconnected-(U1D-IO_L49P_3-PadP12)") (class "Default")
      (node (ref "U1") (pin "P12") (pinfunction "IO_L49P_3_P12") (pintype "bidirectional"))
    )
    (net (code "138") (name "unconnected-(U1D-IO_L50N_3-PadP9)") (class "Default")
      (node (ref "U1") (pin "P9") (pinfunction "IO_L50N_3_P9") (pintype "bidirectional"))
    )
    (net (code "139") (name "unconnected-(U1D-IO_L50P_3-PadP10)") (class "Default")
      (node (ref "U1") (pin "P10") (pinfunction "IO_L50P_3_P10") (pintype "bidirectional"))
    )
    (net (code "140") (name "unconnected-(U1D-IO_L51N_3-PadP7)") (class "Default")
      (node (ref "U1") (pin "P7") (pinfunction "IO_L51N_3_P7") (pintype "bidirectional"))
    )
    (net (code "141") (name "unconnected-(U1D-IO_L51P_3-PadP8)") (class "Default")
      (node (ref "U1") (pin "P8") (pinfunction "IO_L51P_3_P8") (pintype "bidirectional"))
    )
    (net (code "142") (name "unconnected-(U1D-IO_L52N_3-PadP5)") (class "Default")
      (node (ref "U1") (pin "P5") (pinfunction "IO_L52N_3_P5") (pintype "bidirectional"))
    )
    (net (code "143") (name "unconnected-(U1D-IO_L52P_3-PadP6)") (class "Default")
      (node (ref "U1") (pin "P6") (pinfunction "IO_L52P_3_P6") (pintype "bidirectional"))
    )
    (net (code "144") (name "unconnected-(U1D-IO_L83N_VREF_3-PadP1)") (class "Default")
      (node (ref "U1") (pin "P1") (pinfunction "IO_L83N_VREF_3_P1") (pintype "bidirectional"))
    )
    (net (code "145") (name "unconnected-(U1D-IO_L83P_3-PadP2)") (class "Default")
      (node (ref "U1") (pin "P2") (pinfunction "IO_L83P_3_P2") (pintype "bidirectional"))
    )
    (net (code "146") (name "unconnected-(U1F-SUSPEND-PadP73)") (class "Default")
      (node (ref "U1") (pin "P73") (pinfunction "SUSPEND_P73") (pintype "bidirectional"))
    )
    (net (code "147") (name "unconnected-(U1F-TCK-PadP109)") (class "Default")
      (node (ref "U1") (pin "P109") (pinfunction "TCK_P109") (pintype "bidirectional"))
    )
    (net (code "148") (name "unconnected-(U1F-TDI-PadP110)") (class "Default")
      (node (ref "U1") (pin "P110") (pinfunction "TDI_P110") (pintype "bidirectional"))
    )
    (net (code "149") (name "unconnected-(U1F-TDO-PadP106)") (class "Default")
      (node (ref "U1") (pin "P106") (pinfunction "TDO_P106") (pintype "bidirectional"))
    )
    (net (code "150") (name "unconnected-(U1F-TMS-PadP107)") (class "Default")
      (node (ref "U1") (pin "P107") (pinfunction "TMS_P107") (pintype "bidirectional"))
    )
    (net (code "151") (name "unconnected-(U1H-VCCINT-PadP19)") (class "Default")
      (node (ref "U1") (pin "P19") (pinfunction "VCCINT_P19") (pintype "input"))
    )
    (net (code "152") (name "unconnected-(U1H-VCCINT-PadP28)") (class "Default")
      (node (ref "U1") (pin "P28") (pinfunction "VCCINT_P28") (pintype "input"))
    )
    (net (code "153") (name "unconnected-(U1H-VCCINT-PadP52)") (class "Default")
      (node (ref "U1") (pin "P52") (pinfunction "VCCINT_P52") (pintype "input"))
    )
    (net (code "154") (name "unconnected-(U1H-VCCINT-PadP89)") (class "Default")
      (node (ref "U1") (pin "P89") (pinfunction "VCCINT_P89") (pintype "input"))
    )
    (net (code "155") (name "unconnected-(U1H-VCCINT-PadP128)") (class "Default")
      (node (ref "U1") (pin "P128") (pinfunction "VCCINT_P128") (pintype "input"))
    )
  )
)
